# SCH.net
KiCad netlist of a schematic drawn in Altium Designer
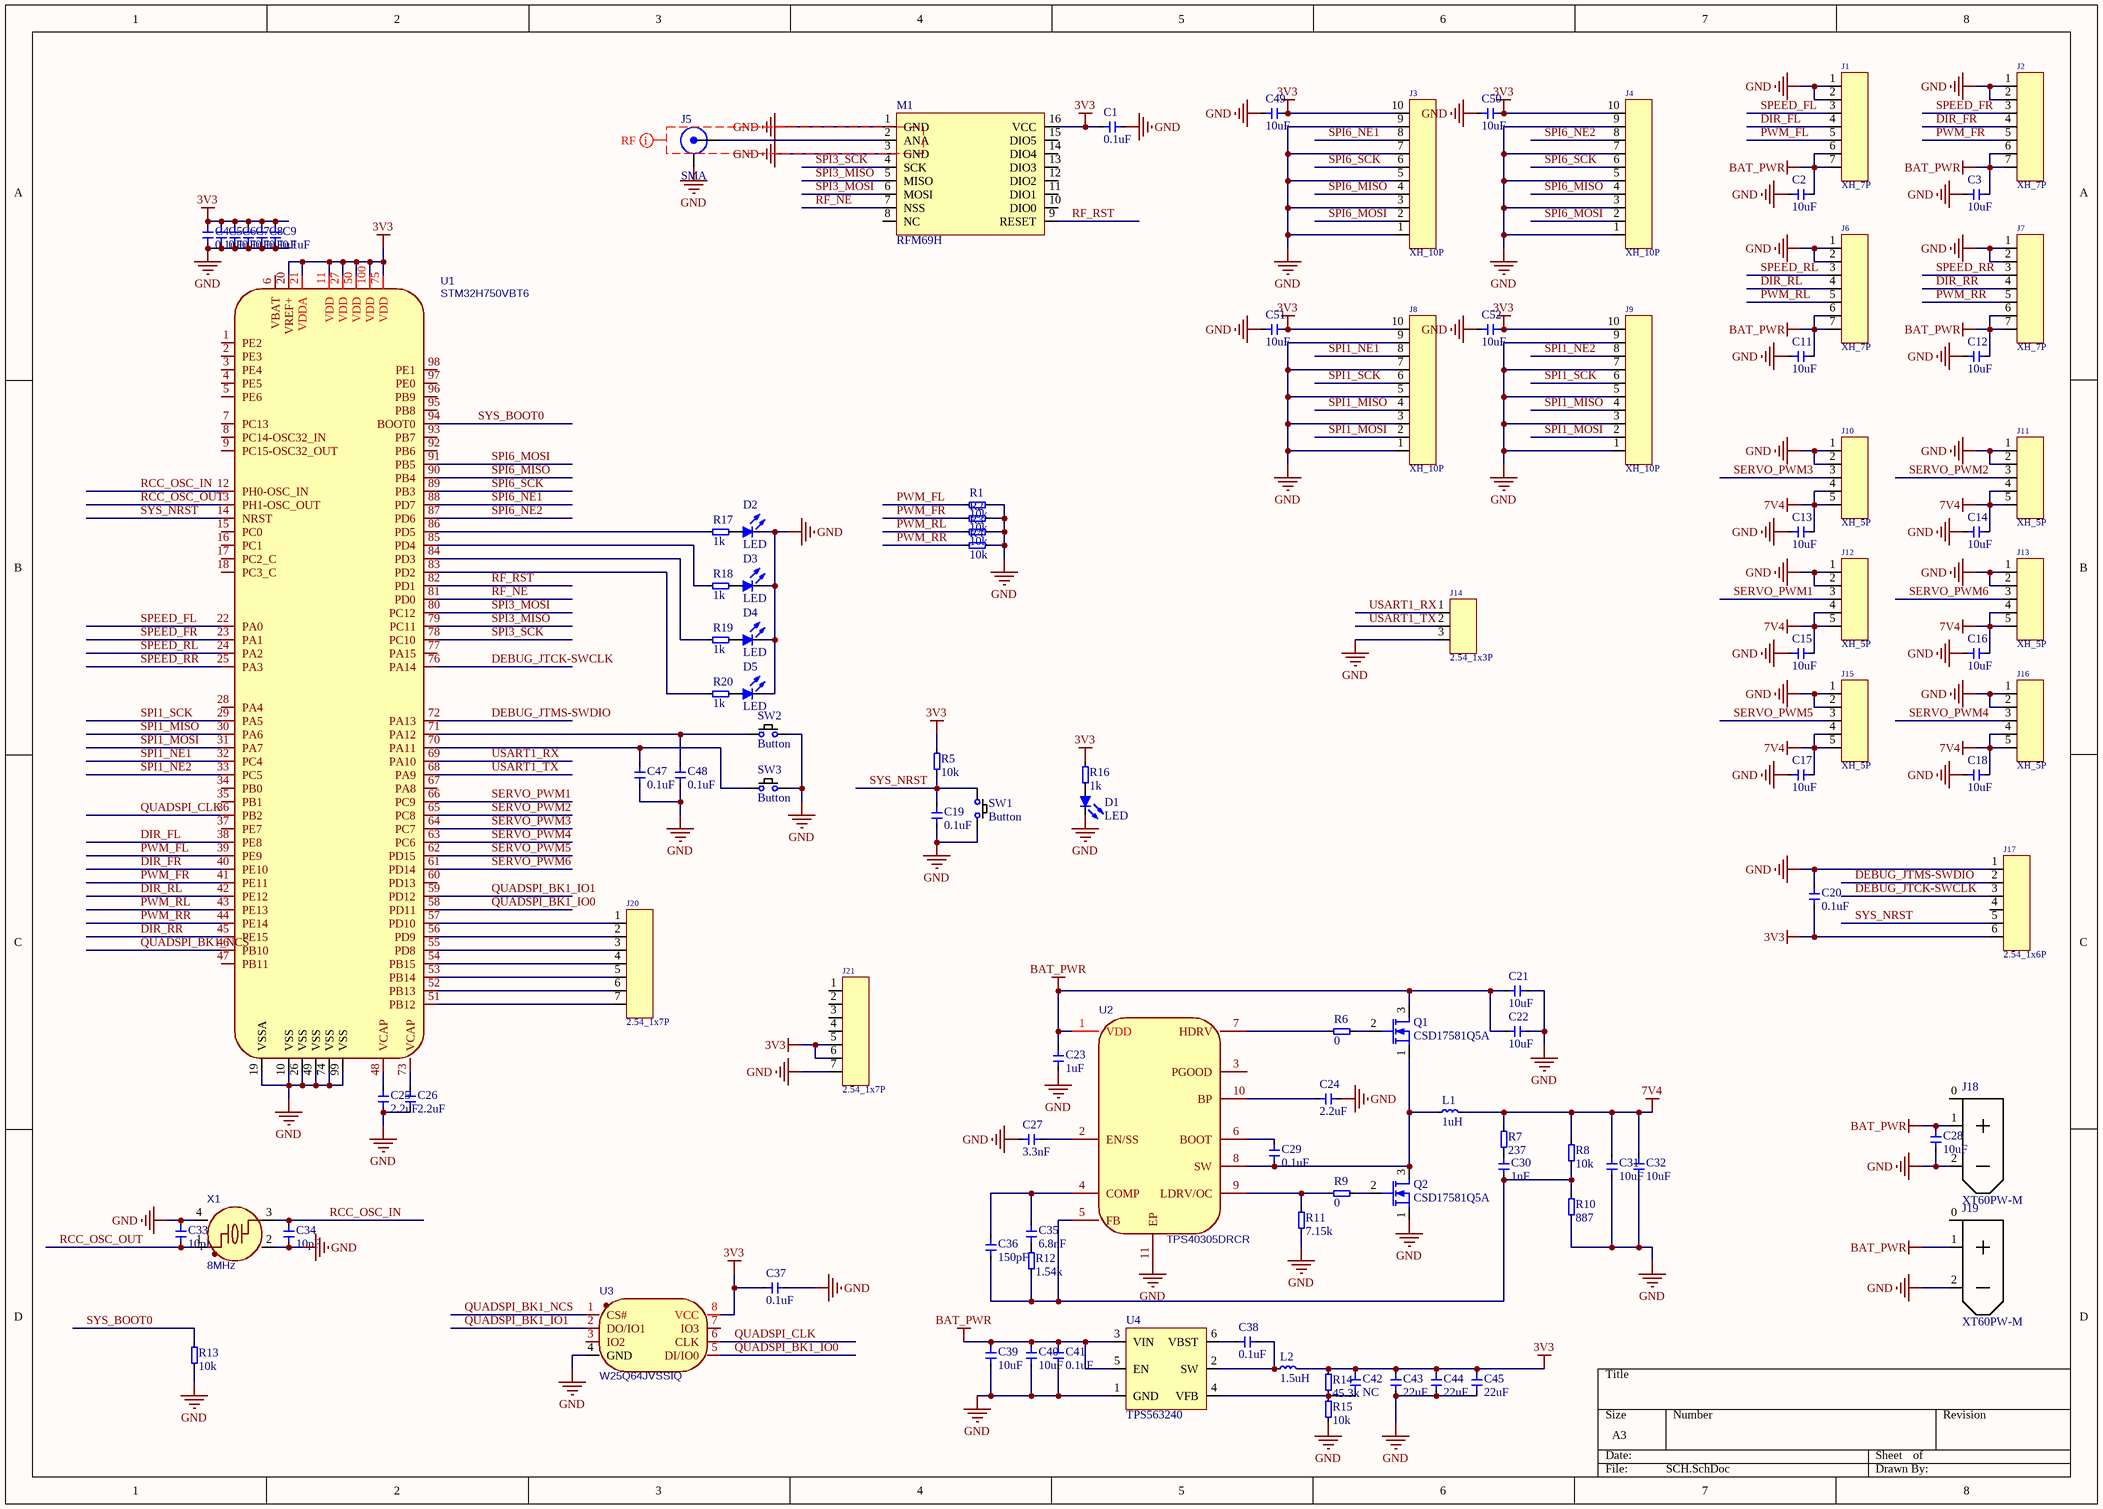
[diagram p0: SCH.SchDoc]

(export (version "E")
  (design (tool "Eeschema 10.0.6"))
  (components
    (comp (ref "C1") (value "0.1uF") (footprint "0402") (libsource (lib "pants1") (part "Cap")))
    (comp (ref "C2") (value "10uF") (footprint "0805") (libsource (lib "pants1") (part "Cap")))
    (comp (ref "C3") (value "10uF") (footprint "0805") (libsource (lib "pants1") (part "Cap")))
    (comp (ref "C4") (value "0.1uF") (footprint "0402") (libsource (lib "pants1") (part "Cap")))
    (comp (ref "C5") (value "0.1uF") (footprint "0402") (libsource (lib "pants1") (part "Cap")))
    (comp (ref "C6") (value "0.1uF") (footprint "0402") (libsource (lib "pants1") (part "Cap")))
    (comp (ref "C7") (value "0.1uF") (footprint "0402") (libsource (lib "pants1") (part "Cap")))
    (comp (ref "C8") (value "0.1uF") (footprint "0402") (libsource (lib "pants1") (part "Cap")))
    (comp (ref "C9") (value "0.1uF") (footprint "0402") (libsource (lib "pants1") (part "Cap")))
    (comp (ref "C11") (value "10uF") (footprint "0805") (libsource (lib "pants1") (part "Cap")))
    (comp (ref "C12") (value "10uF") (footprint "0805") (libsource (lib "pants1") (part "Cap")))
    (comp (ref "C13") (value "10uF") (footprint "0805") (libsource (lib "pants1") (part "Cap")))
    (comp (ref "C14") (value "10uF") (footprint "0805") (libsource (lib "pants1") (part "Cap")))
    (comp (ref "C15") (value "10uF") (footprint "0805") (libsource (lib "pants1") (part "Cap")))
    (comp (ref "C16") (value "10uF") (footprint "0805") (libsource (lib "pants1") (part "Cap")))
    (comp (ref "C17") (value "10uF") (footprint "0805") (libsource (lib "pants1") (part "Cap")))
    (comp (ref "C18") (value "10uF") (footprint "0805") (libsource (lib "pants1") (part "Cap")))
    (comp (ref "C19") (value "0.1uF") (footprint "0402") (libsource (lib "pants1") (part "Cap")))
    (comp (ref "C20") (value "0.1uF") (footprint "0402") (libsource (lib "pants1") (part "Cap")))
    (comp (ref "C21") (value "10uF") (footprint "0805") (libsource (lib "pants1") (part "Cap")))
    (comp (ref "C22") (value "10uF") (footprint "0805") (libsource (lib "pants1") (part "Cap")))
    (comp (ref "C23") (value "1uF") (footprint "0603") (libsource (lib "pants1") (part "Cap")))
    (comp (ref "C24") (value "2.2uF") (footprint "0603") (libsource (lib "pants1") (part "Cap")))
    (comp (ref "C25") (value "2.2uF") (footprint "0402") (libsource (lib "pants1") (part "Cap")))
    (comp (ref "C26") (value "2.2uF") (footprint "0402") (libsource (lib "pants1") (part "Cap")))
    (comp (ref "C27") (value "3.3nF") (footprint "0402") (libsource (lib "pants1") (part "Cap")))
    (comp (ref "C28") (value "10uF") (footprint "0805") (libsource (lib "pants1") (part "Cap")))
    (comp (ref "C29") (value "0.1uF") (footprint "0805") (libsource (lib "pants1") (part "Cap")))
    (comp (ref "C30") (value "1nF") (footprint "0402") (libsource (lib "pants1") (part "Cap")))
    (comp (ref "C31") (value "10uF") (footprint "0805") (libsource (lib "pants1") (part "Cap")))
    (comp (ref "C32") (value "10uF") (footprint "0805") (libsource (lib "pants1") (part "Cap")))
    (comp (ref "C33") (value "10pF") (footprint "0402") (libsource (lib "pants1") (part "Cap")))
    (comp (ref "C34") (value "10pF") (footprint "0402") (libsource (lib "pants1") (part "Cap")))
    (comp (ref "C35") (value "6.8nF") (footprint "0402") (libsource (lib "pants1") (part "Cap")))
    (comp (ref "C36") (value "150pF") (footprint "0402") (libsource (lib "pants1") (part "Cap")))
    (comp (ref "C37") (value "0.1uF") (footprint "0402") (libsource (lib "pants1") (part "Cap")))
    (comp (ref "C38") (value "0.1uF") (footprint "0603") (libsource (lib "pants1") (part "Cap")))
    (comp (ref "C39") (value "10uF") (footprint "0805") (libsource (lib "pants1") (part "Cap")))
    (comp (ref "C40") (value "10uF") (footprint "0805") (libsource (lib "pants1") (part "Cap")))
    (comp (ref "C41") (value "0.1uF") (footprint "0603") (libsource (lib "pants1") (part "Cap")))
    (comp (ref "C42") (value "NC") (footprint "0402") (libsource (lib "pants1") (part "Cap")))
    (comp (ref "C43") (value "22uF") (footprint "0603") (libsource (lib "pants1") (part "Cap")))
    (comp (ref "C44") (value "22uF") (footprint "0603") (libsource (lib "pants1") (part "Cap")))
    (comp (ref "C45") (value "22uF") (footprint "0603") (libsource (lib "pants1") (part "Cap")))
    (comp (ref "C47") (value "0.1uF") (footprint "0402") (libsource (lib "pants1") (part "Cap")))
    (comp (ref "C48") (value "0.1uF") (footprint "0402") (libsource (lib "pants1") (part "Cap")))
    (comp (ref "C49") (value "10uF") (footprint "0603") (libsource (lib "pants1") (part "Cap")))
    (comp (ref "C50") (value "10uF") (footprint "0603") (libsource (lib "pants1") (part "Cap")))
    (comp (ref "C51") (value "10uF") (footprint "0603") (libsource (lib "pants1") (part "Cap")))
    (comp (ref "C52") (value "10uF") (footprint "0603") (libsource (lib "pants1") (part "Cap")))
    (comp (ref "D1") (value "LED") (footprint "0603LED") (libsource (lib "pants1") (part "LED")))
    (comp (ref "D2") (value "LED") (footprint "0603LED") (libsource (lib "pants1") (part "LED")))
    (comp (ref "D3") (value "LED") (footprint "0603LED") (libsource (lib "pants1") (part "LED")))
    (comp (ref "D4") (value "LED") (footprint "0603LED") (libsource (lib "pants1") (part "LED")))
    (comp (ref "D5") (value "LED") (footprint "0603LED") (libsource (lib "pants1") (part "LED")))
    (comp (ref "J1") (value "XH_7P") (footprint "XH_7P直插立式") (libsource (lib "XH_Connectors") (part "XH_7P")))
    (comp (ref "J2") (value "XH_7P") (footprint "XH_7P直插立式") (libsource (lib "XH_Connectors") (part "XH_7P")))
    (comp (ref "J3")
      (value "XH_10P")
      (footprint "XH_10P直插立式")
      (libsource (lib "XH_Connectors") (part "XH_10P"))
    )
    (comp (ref "J4")
      (value "XH_10P")
      (footprint "XH_10P直插立式")
      (libsource (lib "XH_Connectors") (part "XH_10P"))
    )
    (comp (ref "J5") (value "SMA") (footprint "SMA_Edge") (libsource (lib "pants1") (part "Coax")))
    (comp (ref "J6") (value "XH_7P") (footprint "XH_7P直插立式") (libsource (lib "XH_Connectors") (part "XH_7P")))
    (comp (ref "J7") (value "XH_7P") (footprint "XH_7P直插立式") (libsource (lib "XH_Connectors") (part "XH_7P")))
    (comp (ref "J8")
      (value "XH_10P")
      (footprint "XH_10P直插立式")
      (libsource (lib "XH_Connectors") (part "XH_10P"))
    )
    (comp (ref "J9")
      (value "XH_10P")
      (footprint "XH_10P直插立式")
      (libsource (lib "XH_Connectors") (part "XH_10P"))
    )
    (comp (ref "J10")
      (value "XH_5P")
      (footprint "XH_5P直插立式")
      (libsource (lib "XH_Connectors") (part "XH_5P"))
    )
    (comp (ref "J11")
      (value "XH_5P")
      (footprint "XH_5P直插立式")
      (libsource (lib "XH_Connectors") (part "XH_5P"))
    )
    (comp (ref "J12")
      (value "XH_5P")
      (footprint "XH_5P直插立式")
      (libsource (lib "XH_Connectors") (part "XH_5P"))
    )
    (comp (ref "J13")
      (value "XH_5P")
      (footprint "XH_5P直插立式")
      (libsource (lib "XH_Connectors") (part "XH_5P"))
    )
    (comp (ref "J14")
      (value "2.54_1x3P")
      (footprint "2.54排针_1x3立式")
      (libsource (lib "2.54排针") (part "2.54_1x3P"))
    )
    (comp (ref "J15")
      (value "XH_5P")
      (footprint "XH_5P直插立式")
      (libsource (lib "XH_Connectors") (part "XH_5P"))
    )
    (comp (ref "J16")
      (value "XH_5P")
      (footprint "XH_5P直插立式")
      (libsource (lib "XH_Connectors") (part "XH_5P"))
    )
    (comp (ref "J17")
      (value "2.54_1x6P")
      (footprint "2.54排针_1x6立式")
      (libsource (lib "2.54排针") (part "2.54_1x6P"))
    )
    (comp (ref "J18") (value "XT60PW-M") (footprint "XT60PW-M20") (libsource (lib "XT60") (part "XT60PW-M")))
    (comp (ref "J19") (value "XT60PW-M") (footprint "XT60PW-M20") (libsource (lib "XT60") (part "XT60PW-M")))
    (comp (ref "J20")
      (value "2.54_1x7P")
      (footprint "2.54排针_1x7立式")
      (libsource (lib "2.54排针") (part "2.54_1x7P"))
    )
    (comp (ref "J21")
      (value "2.54_1x7P")
      (footprint "2.54排针_1x7立式")
      (libsource (lib "2.54排针") (part "2.54_1x7P"))
    )
    (comp (ref "L1")
      (value "1uH")
      (footprint "IND-SMD_L11.5-W10.5_1004")
      (description "Inductor")
      (libsource (lib "pants1") (part "Inductor"))
    )
    (comp (ref "L2")
      (value "1.5uH")
      (footprint "IND-SMD_L7.1-W6.6_0630")
      (description "Inductor")
      (libsource (lib "pants1") (part "Inductor"))
    )
    (comp (ref "M1") (value "RFM69H") (footprint "RFM69H") (libsource (lib "pants1") (part "RFM69H")))
    (comp (ref "Q1")
      (value "CSD17581Q5A")
      (footprint "SON-8_L5.0-W6.0-P1.27-BL_MOSFET")
      (libsource (lib "pants1") (part "MOS_N_SON8"))
    )
    (comp (ref "Q2")
      (value "CSD17581Q5A")
      (footprint "SON-8_L5.0-W6.0-P1.27-BL_MOSFET")
      (libsource (lib "pants1") (part "MOS_N_SON8"))
    )
    (comp (ref "R1")
      (value "10k")
      (footprint "0402")
      (description "Resistor")
      (libsource (lib "") (part "Res_1"))
    )
    (comp (ref "R2")
      (value "10k")
      (footprint "0402")
      (description "Resistor")
      (libsource (lib "") (part "Res_1"))
    )
    (comp (ref "R3")
      (value "10k")
      (footprint "0402")
      (description "Resistor")
      (libsource (lib "") (part "Res_1"))
    )
    (comp (ref "R4")
      (value "10k")
      (footprint "0402")
      (description "Resistor")
      (libsource (lib "") (part "Res_1"))
    )
    (comp (ref "R5")
      (value "10k")
      (footprint "0402")
      (description "Resistor")
      (libsource (lib "pants1") (part "Res"))
    )
    (comp (ref "R6")
      (value "0")
      (footprint "0402")
      (description "Resistor")
      (libsource (lib "") (part "Res_1"))
    )
    (comp (ref "R7")
      (value "237")
      (footprint "0402")
      (description "Resistor")
      (libsource (lib "pants1") (part "Res"))
    )
    (comp (ref "R8")
      (value "10k")
      (footprint "0402")
      (description "Resistor")
      (libsource (lib "pants1") (part "Res"))
    )
    (comp (ref "R9")
      (value "0")
      (footprint "0402")
      (description "Resistor")
      (libsource (lib "") (part "Res_1"))
    )
    (comp (ref "R10")
      (value "887")
      (footprint "0402")
      (description "Resistor")
      (libsource (lib "pants1") (part "Res"))
    )
    (comp (ref "R11")
      (value "7.15k")
      (footprint "0402")
      (description "Resistor")
      (libsource (lib "pants1") (part "Res"))
    )
    (comp (ref "R12")
      (value "1.54k")
      (footprint "0402")
      (description "Resistor")
      (libsource (lib "pants1") (part "Res"))
    )
    (comp (ref "R13")
      (value "10k")
      (footprint "0402")
      (description "Resistor")
      (libsource (lib "pants1") (part "Res"))
    )
    (comp (ref "R14")
      (value "45.3k")
      (footprint "0402")
      (description "Resistor")
      (libsource (lib "pants1") (part "Res"))
    )
    (comp (ref "R15")
      (value "10k")
      (footprint "0402")
      (description "Resistor")
      (libsource (lib "pants1") (part "Res"))
    )
    (comp (ref "R16")
      (value "1k")
      (footprint "0402")
      (description "Resistor")
      (libsource (lib "pants1") (part "Res"))
    )
    (comp (ref "R17")
      (value "1k")
      (footprint "0402")
      (description "Resistor")
      (libsource (lib "") (part "Res_2"))
    )
    (comp (ref "R18")
      (value "1k")
      (footprint "0402")
      (description "Resistor")
      (libsource (lib "") (part "Res_2"))
    )
    (comp (ref "R19")
      (value "1k")
      (footprint "0402")
      (description "Resistor")
      (libsource (lib "") (part "Res_2"))
    )
    (comp (ref "R20")
      (value "1k")
      (footprint "0402")
      (description "Resistor")
      (libsource (lib "") (part "Res_2"))
    )
    (comp (ref "SW1")
      (value "Button")
      (footprint "KEY-SMD_4P-L6.0-W6.0-P4.50-LS8.6")
      (libsource (lib "pants1") (part "Button"))
    )
    (comp (ref "SW2")
      (value "Button")
      (footprint "KEY-SMD_4P-L6.0-W6.0-P4.50-LS8.6")
      (libsource (lib "pants1") (part "Button"))
    )
    (comp (ref "SW3")
      (value "Button")
      (footprint "KEY-SMD_4P-L6.0-W6.0-P4.50-LS8.6")
      (libsource (lib "pants1") (part "Button"))
    )
    (comp (ref "U1")
      (value "STM32H750VBT6")
      (footprint "LQFP-100_L14.0-W14.0-P0.50-LS16.0-BL")
      (fields (field (name "BOM_SUPPLIER PART") "C404010") (field (name "CONTRIBUTOR") "LCSC"))
      (libsource (lib "pants1") (part "STM32H750VBT6"))
    )
    (comp (ref "U2")
      (value "TPS40305DRCR")
      (footprint "VSON-10_L3.0-W3.0-P0.50-TL-EP")
      (fields (field (name "BOM_SUPPLIER PART") "C140285") (field (name "CONTRIBUTOR") "LCSC"))
      (libsource (lib "pants1") (part "TPS40305DRCR"))
    )
    (comp (ref "U3")
      (value "W25Q64JVSSIQ")
      (footprint "SOP-8_L5.3-W5.3-P1.27-LS8.0-BL")
      (fields (field (name "BOM_SUPPLIER PART") "C83140"))
      (libsource (lib "pants1") (part "W25Q64JVSSIQ"))
    )
    (comp (ref "U4")
      (value "TPS563240")
      (footprint "SOT-23-6_L2.9-W1.6-P0.95-LS2.8-BR")
      (libsource (lib "pants1") (part "TPS563240"))
    )
    (comp (ref "X1")
      (value "8MHz")
      (footprint "OSC-SMD_4P-L3.2-W2.5-BL")
      (fields
        (field (name "BOM_SUPPLIER PART") "C518156")
        (field (name "BOM_MANUFACTURER PART") "3225-8.00-20-10-10/A")
        (field (name "CONTRIBUTOR") "LCSC")
      )
      (libsource (lib "pants1") (part "Crystal_4P"))
    )
  )
  (nets
    (net (code "1") (name "/DEBUG_JTCK-SWCLK") (class "Default")
      (node (ref "J17") (pin "3") (pinfunction "3_3") (pintype "passive"))
      (node (ref "U1") (pin "76") (pinfunction "PA14_76") (pintype "passive"))
    )
    (net (code "2") (name "/DEBUG_JTMS-SWDIO") (class "Default")
      (node (ref "J17") (pin "2") (pinfunction "2_2") (pintype "passive"))
      (node (ref "U1") (pin "72") (pinfunction "PA13_72") (pintype "passive"))
    )
    (net (code "3") (name "/DIR_FL") (class "Default")
      (node (ref "J1") (pin "4") (pinfunction "4_4") (pintype "passive"))
      (node (ref "U1") (pin "38") (pinfunction "PE8_38") (pintype "passive"))
    )
    (net (code "4") (name "/DIR_FR") (class "Default")
      (node (ref "J2") (pin "4") (pinfunction "4_4") (pintype "passive"))
      (node (ref "U1") (pin "40") (pinfunction "PE10_40") (pintype "passive"))
    )
    (net (code "5") (name "/DIR_RL") (class "Default")
      (node (ref "J6") (pin "4") (pinfunction "4_4") (pintype "passive"))
      (node (ref "U1") (pin "42") (pinfunction "PE12_42") (pintype "passive"))
    )
    (net (code "6") (name "/DIR_RR") (class "Default")
      (node (ref "J7") (pin "4") (pinfunction "4_4") (pintype "passive"))
      (node (ref "U1") (pin "45") (pinfunction "PE15_45") (pintype "passive"))
    )
    (net (code "7") (name "/PWM_FL") (class "Default")
      (node (ref "J1") (pin "5") (pinfunction "5_5") (pintype "passive"))
      (node (ref "R1") (pin "1") (pinfunction "1_1") (pintype "passive"))
      (node (ref "U1") (pin "39") (pinfunction "PE9_39") (pintype "passive"))
    )
    (net (code "8") (name "/PWM_FR") (class "Default")
      (node (ref "J2") (pin "5") (pinfunction "5_5") (pintype "passive"))
      (node (ref "R2") (pin "1") (pinfunction "1_1") (pintype "passive"))
      (node (ref "U1") (pin "41") (pinfunction "PE11_41") (pintype "passive"))
    )
    (net (code "9") (name "/PWM_RL") (class "Default")
      (node (ref "J6") (pin "5") (pinfunction "5_5") (pintype "passive"))
      (node (ref "R3") (pin "1") (pinfunction "1_1") (pintype "passive"))
      (node (ref "U1") (pin "43") (pinfunction "PE13_43") (pintype "passive"))
    )
    (net (code "10") (name "/PWM_RR") (class "Default")
      (node (ref "J7") (pin "5") (pinfunction "5_5") (pintype "passive"))
      (node (ref "R4") (pin "1") (pinfunction "1_1") (pintype "passive"))
      (node (ref "U1") (pin "44") (pinfunction "PE14_44") (pintype "passive"))
    )
    (net (code "11") (name "/QUADSPI_BK1_IO0") (class "Default")
      (node (ref "U1") (pin "58") (pinfunction "PD11_58") (pintype "passive"))
      (node (ref "U3") (pin "5") (pinfunction "DI/IO0_5") (pintype "passive"))
    )
    (net (code "12") (name "/QUADSPI_BK1_IO1") (class "Default")
      (node (ref "U1") (pin "59") (pinfunction "PD12_59") (pintype "passive"))
      (node (ref "U3") (pin "2") (pinfunction "DO/IO1_2") (pintype "passive"))
    )
    (net (code "13") (name "/QUADSPI_BK1_NCS") (class "Default")
      (node (ref "U1") (pin "46") (pinfunction "PB10_46") (pintype "passive"))
      (node (ref "U3") (pin "1") (pinfunction "CS#_1") (pintype "passive"))
    )
    (net (code "14") (name "/QUADSPI_CLK") (class "Default")
      (node (ref "U1") (pin "36") (pinfunction "PB2_36") (pintype "passive"))
      (node (ref "U3") (pin "6") (pinfunction "CLK_6") (pintype "passive"))
    )
    (net (code "15") (name "/RCC_OSC_IN") (class "Default")
      (node (ref "C34") (pin "2") (pinfunction "2_2") (pintype "passive"))
      (node (ref "U1") (pin "12") (pinfunction "PH0-OSC_IN_12") (pintype "passive"))
      (node (ref "X1") (pin "3") (pinfunction "3_3") (pintype "passive"))
    )
    (net (code "16") (name "/RCC_OSC_OUT") (class "Default")
      (node (ref "C33") (pin "1") (pinfunction "1_1") (pintype "passive"))
      (node (ref "U1") (pin "13") (pinfunction "PH1-OSC_OUT_13") (pintype "passive"))
      (node (ref "X1") (pin "1") (pinfunction "1_1") (pintype "passive"))
    )
    (net (code "17") (name "/RF_NE") (class "Default")
      (node (ref "M1") (pin "7") (pinfunction "NSS_7") (pintype "passive"))
      (node (ref "U1") (pin "81") (pinfunction "PD0_81") (pintype "passive"))
    )
    (net (code "18") (name "/RF_RST") (class "Default")
      (node (ref "M1") (pin "9") (pinfunction "RESET_9") (pintype "passive"))
      (node (ref "U1") (pin "82") (pinfunction "PD1_82") (pintype "passive"))
    )
    (net (code "19") (name "/SERVO_PWM1") (class "Default")
      (node (ref "J12") (pin "3") (pinfunction "3_3") (pintype "passive"))
      (node (ref "U1") (pin "66") (pinfunction "PC9_66") (pintype "passive"))
    )
    (net (code "20") (name "/SERVO_PWM2") (class "Default")
      (node (ref "J11") (pin "3") (pinfunction "3_3") (pintype "passive"))
      (node (ref "U1") (pin "65") (pinfunction "PC8_65") (pintype "passive"))
    )
    (net (code "21") (name "/SERVO_PWM3") (class "Default")
      (node (ref "J10") (pin "3") (pinfunction "3_3") (pintype "passive"))
      (node (ref "U1") (pin "64") (pinfunction "PC7_64") (pintype "passive"))
    )
    (net (code "22") (name "/SERVO_PWM4") (class "Default")
      (node (ref "J16") (pin "3") (pinfunction "3_3") (pintype "passive"))
      (node (ref "U1") (pin "63") (pinfunction "PC6_63") (pintype "passive"))
    )
    (net (code "23") (name "/SERVO_PWM5") (class "Default")
      (node (ref "J15") (pin "3") (pinfunction "3_3") (pintype "passive"))
      (node (ref "U1") (pin "62") (pinfunction "PD15_62") (pintype "passive"))
    )
    (net (code "24") (name "/SERVO_PWM6") (class "Default")
      (node (ref "J13") (pin "3") (pinfunction "3_3") (pintype "passive"))
      (node (ref "U1") (pin "61") (pinfunction "PD14_61") (pintype "passive"))
    )
    (net (code "25") (name "/SPEED_FL") (class "Default")
      (node (ref "J1") (pin "3") (pinfunction "3_3") (pintype "passive"))
      (node (ref "U1") (pin "22") (pinfunction "PA0_22") (pintype "passive"))
    )
    (net (code "26") (name "/SPEED_FR") (class "Default")
      (node (ref "J2") (pin "3") (pinfunction "3_3") (pintype "passive"))
      (node (ref "U1") (pin "23") (pinfunction "PA1_23") (pintype "passive"))
    )
    (net (code "27") (name "/SPEED_RL") (class "Default")
      (node (ref "J6") (pin "3") (pinfunction "3_3") (pintype "passive"))
      (node (ref "U1") (pin "24") (pinfunction "PA2_24") (pintype "passive"))
    )
    (net (code "28") (name "/SPEED_RR") (class "Default")
      (node (ref "J7") (pin "3") (pinfunction "3_3") (pintype "passive"))
      (node (ref "U1") (pin "25") (pinfunction "PA3_25") (pintype "passive"))
    )
    (net (code "29") (name "/SPI1_MISO") (class "Default")
      (node (ref "J8") (pin "4") (pinfunction "4_4") (pintype "passive"))
      (node (ref "J9") (pin "4") (pinfunction "4_4") (pintype "passive"))
      (node (ref "U1") (pin "30") (pinfunction "PA6_30") (pintype "passive"))
    )
    (net (code "30") (name "/SPI1_MOSI") (class "Default")
      (node (ref "J8") (pin "2") (pinfunction "2_2") (pintype "passive"))
      (node (ref "J9") (pin "2") (pinfunction "2_2") (pintype "passive"))
      (node (ref "U1") (pin "31") (pinfunction "PA7_31") (pintype "passive"))
    )
    (net (code "31") (name "/SPI1_NE1") (class "Default")
      (node (ref "J8") (pin "8") (pinfunction "8_8") (pintype "passive"))
      (node (ref "U1") (pin "32") (pinfunction "PC4_32") (pintype "passive"))
    )
    (net (code "32") (name "/SPI1_NE2") (class "Default")
      (node (ref "J9") (pin "8") (pinfunction "8_8") (pintype "passive"))
      (node (ref "U1") (pin "33") (pinfunction "PC5_33") (pintype "passive"))
    )
    (net (code "33") (name "/SPI1_SCK") (class "Default")
      (node (ref "J8") (pin "6") (pinfunction "6_6") (pintype "passive"))
      (node (ref "J9") (pin "6") (pinfunction "6_6") (pintype "passive"))
      (node (ref "U1") (pin "29") (pinfunction "PA5_29") (pintype "passive"))
    )
    (net (code "34") (name "/SPI3_MISO") (class "Default")
      (node (ref "M1") (pin "5") (pinfunction "MISO_5") (pintype "passive"))
      (node (ref "U1") (pin "79") (pinfunction "PC11_79") (pintype "passive"))
    )
    (net (code "35") (name "/SPI3_MOSI") (class "Default")
      (node (ref "M1") (pin "6") (pinfunction "MOSI_6") (pintype "passive"))
      (node (ref "U1") (pin "80") (pinfunction "PC12_80") (pintype "passive"))
    )
    (net (code "36") (name "/SPI3_SCK") (class "Default")
      (node (ref "M1") (pin "4") (pinfunction "SCK_4") (pintype "passive"))
      (node (ref "U1") (pin "78") (pinfunction "PC10_78") (pintype "passive"))
    )
    (net (code "37") (name "/SPI6_MISO") (class "Default")
      (node (ref "J3") (pin "4") (pinfunction "4_4") (pintype "passive"))
      (node (ref "J4") (pin "4") (pinfunction "4_4") (pintype "passive"))
      (node (ref "U1") (pin "90") (pinfunction "PB4_90") (pintype "passive"))
    )
    (net (code "38") (name "/SPI6_MOSI") (class "Default")
      (node (ref "J3") (pin "2") (pinfunction "2_2") (pintype "passive"))
      (node (ref "J4") (pin "2") (pinfunction "2_2") (pintype "passive"))
      (node (ref "U1") (pin "91") (pinfunction "PB5_91") (pintype "passive"))
    )
    (net (code "39") (name "/SPI6_NE1") (class "Default")
      (node (ref "J3") (pin "8") (pinfunction "8_8") (pintype "passive"))
      (node (ref "U1") (pin "88") (pinfunction "PD7_88") (pintype "passive"))
    )
    (net (code "40") (name "/SPI6_NE2") (class "Default")
      (node (ref "J4") (pin "8") (pinfunction "8_8") (pintype "passive"))
      (node (ref "U1") (pin "87") (pinfunction "PD6_87") (pintype "passive"))
    )
    (net (code "41") (name "/SPI6_SCK") (class "Default")
      (node (ref "J3") (pin "6") (pinfunction "6_6") (pintype "passive"))
      (node (ref "J4") (pin "6") (pinfunction "6_6") (pintype "passive"))
      (node (ref "U1") (pin "89") (pinfunction "PB3_89") (pintype "passive"))
    )
    (net (code "42") (name "/SYS_BOOT0") (class "Default")
      (node (ref "R13") (pin "2") (pinfunction "2_2") (pintype "passive"))
      (node (ref "U1") (pin "94") (pinfunction "BOOT0_94") (pintype "passive"))
    )
    (net (code "43") (name "/SYS_NRST") (class "Default")
      (node (ref "C19") (pin "2") (pinfunction "2_2") (pintype "passive"))
      (node (ref "J17") (pin "5") (pinfunction "5_5") (pintype "passive"))
      (node (ref "R5") (pin "1") (pinfunction "1_1") (pintype "passive"))
      (node (ref "SW1") (pin "1") (pinfunction "1_1") (pintype "passive"))
      (node (ref "U1") (pin "14") (pinfunction "NRST_14") (pintype "passive"))
    )
    (net (code "44") (name "/USART1_RX") (class "Default")
      (node (ref "J14") (pin "1") (pinfunction "1_1") (pintype "passive"))
      (node (ref "U1") (pin "69") (pinfunction "PA10_69") (pintype "passive"))
    )
    (net (code "45") (name "/USART1_TX") (class "Default")
      (node (ref "J14") (pin "2") (pinfunction "2_2") (pintype "passive"))
      (node (ref "U1") (pin "68") (pinfunction "PA9_68") (pintype "passive"))
    )
    (net (code "46") (name "3V3") (class "Default")
      (node (ref "C1") (pin "2") (pinfunction "2_2") (pintype "passive"))
      (node (ref "C20") (pin "1") (pinfunction "1_1") (pintype "passive"))
      (node (ref "C37") (pin "1") (pinfunction "1_1") (pintype "passive"))
      (node (ref "C4") (pin "2") (pinfunction "2_2") (pintype "passive"))
      (node (ref "C42") (pin "2") (pinfunction "2_2") (pintype "passive"))
      (node (ref "C43") (pin "2") (pinfunction "2_2") (pintype "passive"))
      (node (ref "C44") (pin "2") (pinfunction "2_2") (pintype "passive"))
      (node (ref "C45") (pin "2") (pinfunction "2_2") (pintype "passive"))
      (node (ref "C49") (pin "2") (pinfunction "2_2") (pintype "passive"))
      (node (ref "C5") (pin "2") (pinfunction "2_2") (pintype "passive"))
      (node (ref "C50") (pin "2") (pinfunction "2_2") (pintype "passive"))
      (node (ref "C51") (pin "2") (pinfunction "2_2") (pintype "passive"))
      (node (ref "C52") (pin "2") (pinfunction "2_2") (pintype "passive"))
      (node (ref "C6") (pin "2") (pinfunction "2_2") (pintype "passive"))
      (node (ref "C7") (pin "2") (pinfunction "2_2") (pintype "passive"))
      (node (ref "C8") (pin "2") (pinfunction "2_2") (pintype "passive"))
      (node (ref "C9") (pin "2") (pinfunction "2_2") (pintype "passive"))
      (node (ref "J17") (pin "6") (pinfunction "6_6") (pintype "passive"))
      (node (ref "J21") (pin "5") (pinfunction "5_5") (pintype "passive"))
      (node (ref "J21") (pin "6") (pinfunction "6_6") (pintype "passive"))
      (node (ref "J3") (pin "10") (pinfunction "10_10") (pintype "passive"))
      (node (ref "J4") (pin "10") (pinfunction "10_10") (pintype "passive"))
      (node (ref "J8") (pin "10") (pinfunction "10_10") (pintype "passive"))
      (node (ref "J9") (pin "10") (pinfunction "10_10") (pintype "passive"))
      (node (ref "L2") (pin "2") (pinfunction "2_2") (pintype "passive"))
      (node (ref "M1") (pin "16") (pinfunction "VCC_16") (pintype "passive"))
      (node (ref "R14") (pin "2") (pinfunction "2_2") (pintype "passive"))
      (node (ref "R16") (pin "2") (pinfunction "2_2") (pintype "passive"))
      (node (ref "R5") (pin "2") (pinfunction "2_2") (pintype "passive"))
      (node (ref "U1") (pin "100") (pinfunction "VDD_100") (pintype "passive"))
      (node (ref "U1") (pin "11") (pinfunction "VDD_11") (pintype "passive"))
      (node (ref "U1") (pin "20") (pinfunction "VREF+_20") (pintype "passive"))
      (node (ref "U1") (pin "21") (pinfunction "VDDA_21") (pintype "passive"))
      (node (ref "U1") (pin "27") (pinfunction "VDD_27") (pintype "passive"))
      (node (ref "U1") (pin "50") (pinfunction "VDD_50") (pintype "passive"))
      (node (ref "U1") (pin "75") (pinfunction "VDD_75") (pintype "passive"))
      (node (ref "U3") (pin "8") (pinfunction "VCC_8") (pintype "passive"))
    )
    (net (code "47") (name "7V4") (class "Default")
      (node (ref "C13") (pin "2") (pinfunction "2_2") (pintype "passive"))
      (node (ref "C14") (pin "2") (pinfunction "2_2") (pintype "passive"))
      (node (ref "C15") (pin "2") (pinfunction "2_2") (pintype "passive"))
      (node (ref "C16") (pin "2") (pinfunction "2_2") (pintype "passive"))
      (node (ref "C17") (pin "2") (pinfunction "2_2") (pintype "passive"))
      (node (ref "C18") (pin "2") (pinfunction "2_2") (pintype "passive"))
      (node (ref "C31") (pin "1") (pinfunction "1_1") (pintype "passive"))
      (node (ref "C32") (pin "1") (pinfunction "1_1") (pintype "passive"))
      (node (ref "J10") (pin "4") (pinfunction "4_4") (pintype "passive"))
      (node (ref "J10") (pin "5") (pinfunction "5_5") (pintype "passive"))
      (node (ref "J11") (pin "4") (pinfunction "4_4") (pintype "passive"))
      (node (ref "J11") (pin "5") (pinfunction "5_5") (pintype "passive"))
      (node (ref "J12") (pin "4") (pinfunction "4_4") (pintype "passive"))
      (node (ref "J12") (pin "5") (pinfunction "5_5") (pintype "passive"))
      (node (ref "J13") (pin "4") (pinfunction "4_4") (pintype "passive"))
      (node (ref "J13") (pin "5") (pinfunction "5_5") (pintype "passive"))
      (node (ref "J15") (pin "4") (pinfunction "4_4") (pintype "passive"))
      (node (ref "J15") (pin "5") (pinfunction "5_5") (pintype "passive"))
      (node (ref "J16") (pin "4") (pinfunction "4_4") (pintype "passive"))
      (node (ref "J16") (pin "5") (pinfunction "5_5") (pintype "passive"))
      (node (ref "L1") (pin "2") (pinfunction "2_2") (pintype "passive"))
      (node (ref "R7") (pin "2") (pinfunction "2_2") (pintype "passive"))
      (node (ref "R8") (pin "2") (pinfunction "2_2") (pintype "passive"))
    )
    (net (code "48") (name "BAT_PWR") (class "Default")
      (node (ref "C11") (pin "2") (pinfunction "2_2") (pintype "passive"))
      (node (ref "C12") (pin "2") (pinfunction "2_2") (pintype "passive"))
      (node (ref "C2") (pin "2") (pinfunction "2_2") (pintype "passive"))
      (node (ref "C21") (pin "2") (pinfunction "2_2") (pintype "passive"))
      (node (ref "C22") (pin "2") (pinfunction "2_2") (pintype "passive"))
      (node (ref "C23") (pin "2") (pinfunction "2_2") (pintype "passive"))
      (node (ref "C28") (pin "1") (pinfunction "1_1") (pintype "passive"))
      (node (ref "C3") (pin "2") (pinfunction "2_2") (pintype "passive"))
      (node (ref "C39") (pin "2") (pinfunction "2_2") (pintype "passive"))
      (node (ref "C40") (pin "2") (pinfunction "2_2") (pintype "passive"))
      (node (ref "C41") (pin "1") (pinfunction "1_1") (pintype "passive"))
      (node (ref "J1") (pin "6") (pinfunction "6_6") (pintype "passive"))
      (node (ref "J1") (pin "7") (pinfunction "7_7") (pintype "passive"))
      (node (ref "J18") (pin "1") (pinfunction "1_1") (pintype "passive"))
      (node (ref "J19") (pin "1") (pinfunction "1_1") (pintype "passive"))
      (node (ref "J2") (pin "6") (pinfunction "6_6") (pintype "passive"))
      (node (ref "J2") (pin "7") (pinfunction "7_7") (pintype "passive"))
      (node (ref "J6") (pin "6") (pinfunction "6_6") (pintype "passive"))
      (node (ref "J6") (pin "7") (pinfunction "7_7") (pintype "passive"))
      (node (ref "J7") (pin "6") (pinfunction "6_6") (pintype "passive"))
      (node (ref "J7") (pin "7") (pinfunction "7_7") (pintype "passive"))
      (node (ref "Q1") (pin "3") (pinfunction "D_3") (pintype "passive"))
      (node (ref "U2") (pin "1") (pinfunction "VDD_1") (pintype "passive"))
      (node (ref "U4") (pin "3") (pinfunction "VIN_3") (pintype "passive"))
      (node (ref "U4") (pin "5") (pinfunction "EN_5") (pintype "passive"))
    )
    (net (code "49") (name "GND") (class "Default")
      (node (ref "C1") (pin "1") (pinfunction "1_1") (pintype "passive"))
      (node (ref "C11") (pin "1") (pinfunction "1_1") (pintype "passive"))
      (node (ref "C12") (pin "1") (pinfunction "1_1") (pintype "passive"))
      (node (ref "C13") (pin "1") (pinfunction "1_1") (pintype "passive"))
      (node (ref "C14") (pin "1") (pinfunction "1_1") (pintype "passive"))
      (node (ref "C15") (pin "1") (pinfunction "1_1") (pintype "passive"))
      (node (ref "C16") (pin "1") (pinfunction "1_1") (pintype "passive"))
      (node (ref "C17") (pin "1") (pinfunction "1_1") (pintype "passive"))
      (node (ref "C18") (pin "1") (pinfunction "1_1") (pintype "passive"))
      (node (ref "C19") (pin "1") (pinfunction "1_1") (pintype "passive"))
      (node (ref "C2") (pin "1") (pinfunction "1_1") (pintype "passive"))
      (node (ref "C20") (pin "2") (pinfunction "2_2") (pintype "passive"))
      (node (ref "C21") (pin "1") (pinfunction "1_1") (pintype "passive"))
      (node (ref "C22") (pin "1") (pinfunction "1_1") (pintype "passive"))
      (node (ref "C23") (pin "1") (pinfunction "1_1") (pintype "passive"))
      (node (ref "C24") (pin "2") (pinfunction "2_2") (pintype "passive"))
      (node (ref "C25") (pin "1") (pinfunction "1_1") (pintype "passive"))
      (node (ref "C26") (pin "1") (pinfunction "1_1") (pintype "passive"))
      (node (ref "C27") (pin "2") (pinfunction "2_2") (pintype "passive"))
      (node (ref "C28") (pin "2") (pinfunction "2_2") (pintype "passive"))
      (node (ref "C3") (pin "1") (pinfunction "1_1") (pintype "passive"))
      (node (ref "C31") (pin "2") (pinfunction "2_2") (pintype "passive"))
      (node (ref "C32") (pin "2") (pinfunction "2_2") (pintype "passive"))
      (node (ref "C33") (pin "2") (pinfunction "2_2") (pintype "passive"))
      (node (ref "C34") (pin "1") (pinfunction "1_1") (pintype "passive"))
      (node (ref "C37") (pin "2") (pinfunction "2_2") (pintype "passive"))
      (node (ref "C39") (pin "1") (pinfunction "1_1") (pintype "passive"))
      (node (ref "C4") (pin "1") (pinfunction "1_1") (pintype "passive"))
      (node (ref "C40") (pin "1") (pinfunction "1_1") (pintype "passive"))
      (node (ref "C41") (pin "2") (pinfunction "2_2") (pintype "passive"))
      (node (ref "C43") (pin "1") (pinfunction "1_1") (pintype "passive"))
      (node (ref "C44") (pin "1") (pinfunction "1_1") (pintype "passive"))
      (node (ref "C45") (pin "1") (pinfunction "1_1") (pintype "passive"))
      (node (ref "C47") (pin "2") (pinfunction "2_2") (pintype "passive"))
      (node (ref "C48") (pin "2") (pinfunction "2_2") (pintype "passive"))
      (node (ref "C49") (pin "1") (pinfunction "1_1") (pintype "passive"))
      (node (ref "C5") (pin "1") (pinfunction "1_1") (pintype "passive"))
      (node (ref "C50") (pin "1") (pinfunction "1_1") (pintype "passive"))
      (node (ref "C51") (pin "1") (pinfunction "1_1") (pintype "passive"))
      (node (ref "C52") (pin "1") (pinfunction "1_1") (pintype "passive"))
      (node (ref "C6") (pin "1") (pinfunction "1_1") (pintype "passive"))
      (node (ref "C7") (pin "1") (pinfunction "1_1") (pintype "passive"))
      (node (ref "C8") (pin "1") (pinfunction "1_1") (pintype "passive"))
      (node (ref "C9") (pin "1") (pinfunction "1_1") (pintype "passive"))
      (node (ref "D1") (pin "K") (pinfunction "K_K") (pintype "passive"))
      (node (ref "D2") (pin "K") (pinfunction "K_K") (pintype "passive"))
      (node (ref "D3") (pin "K") (pinfunction "K_K") (pintype "passive"))
      (node (ref "D4") (pin "K") (pinfunction "K_K") (pintype "passive"))
      (node (ref "D5") (pin "K") (pinfunction "K_K") (pintype "passive"))
      (node (ref "J1") (pin "1") (pinfunction "1_1") (pintype "passive"))
      (node (ref "J1") (pin "2") (pinfunction "2_2") (pintype "passive"))
      (node (ref "J10") (pin "1") (pinfunction "1_1") (pintype "passive"))
      (node (ref "J10") (pin "2") (pinfunction "2_2") (pintype "passive"))
      (node (ref "J11") (pin "1") (pinfunction "1_1") (pintype "passive"))
      (node (ref "J11") (pin "2") (pinfunction "2_2") (pintype "passive"))
      (node (ref "J12") (pin "1") (pinfunction "1_1") (pintype "passive"))
      (node (ref "J12") (pin "2") (pinfunction "2_2") (pintype "passive"))
      (node (ref "J13") (pin "1") (pinfunction "1_1") (pintype "passive"))
      (node (ref "J13") (pin "2") (pinfunction "2_2") (pintype "passive"))
      (node (ref "J14") (pin "3") (pinfunction "3_3") (pintype "passive"))
      (node (ref "J15") (pin "1") (pinfunction "1_1") (pintype "passive"))
      (node (ref "J15") (pin "2") (pinfunction "2_2") (pintype "passive"))
      (node (ref "J16") (pin "1") (pinfunction "1_1") (pintype "passive"))
      (node (ref "J16") (pin "2") (pinfunction "2_2") (pintype "passive"))
      (node (ref "J17") (pin "1") (pinfunction "1_1") (pintype "passive"))
      (node (ref "J18") (pin "2") (pinfunction "2_2") (pintype "passive"))
      (node (ref "J19") (pin "2") (pinfunction "2_2") (pintype "passive"))
      (node (ref "J2") (pin "1") (pinfunction "1_1") (pintype "passive"))
      (node (ref "J2") (pin "2") (pinfunction "2_2") (pintype "passive"))
      (node (ref "J21") (pin "7") (pinfunction "7_7") (pintype "passive"))
      (node (ref "J3") (pin "1") (pinfunction "1_1") (pintype "passive"))
      (node (ref "J3") (pin "3") (pinfunction "3_3") (pintype "passive"))
      (node (ref "J3") (pin "5") (pinfunction "5_5") (pintype "passive"))
      (node (ref "J3") (pin "7") (pinfunction "7_7") (pintype "passive"))
      (node (ref "J3") (pin "9") (pinfunction "9_9") (pintype "passive"))
      (node (ref "J4") (pin "1") (pinfunction "1_1") (pintype "passive"))
      (node (ref "J4") (pin "3") (pinfunction "3_3") (pintype "passive"))
      (node (ref "J4") (pin "5") (pinfunction "5_5") (pintype "passive"))
      (node (ref "J4") (pin "7") (pinfunction "7_7") (pintype "passive"))
      (node (ref "J4") (pin "9") (pinfunction "9_9") (pintype "passive"))
      (node (ref "J5") (pin "2") (pintype "passive"))
      (node (ref "J6") (pin "1") (pinfunction "1_1") (pintype "passive"))
      (node (ref "J6") (pin "2") (pinfunction "2_2") (pintype "passive"))
      (node (ref "J7") (pin "1") (pinfunction "1_1") (pintype "passive"))
      (node (ref "J7") (pin "2") (pinfunction "2_2") (pintype "passive"))
      (node (ref "J8") (pin "1") (pinfunction "1_1") (pintype "passive"))
      (node (ref "J8") (pin "3") (pinfunction "3_3") (pintype "passive"))
      (node (ref "J8") (pin "5") (pinfunction "5_5") (pintype "passive"))
      (node (ref "J8") (pin "7") (pinfunction "7_7") (pintype "passive"))
      (node (ref "J8") (pin "9") (pinfunction "9_9") (pintype "passive"))
      (node (ref "J9") (pin "1") (pinfunction "1_1") (pintype "passive"))
      (node (ref "J9") (pin "3") (pinfunction "3_3") (pintype "passive"))
      (node (ref "J9") (pin "5") (pinfunction "5_5") (pintype "passive"))
      (node (ref "J9") (pin "7") (pinfunction "7_7") (pintype "passive"))
      (node (ref "J9") (pin "9") (pinfunction "9_9") (pintype "passive"))
      (node (ref "M1") (pin "1") (pinfunction "GND_1") (pintype "passive"))
      (node (ref "M1") (pin "3") (pinfunction "GND_3") (pintype "passive"))
      (node (ref "Q2") (pin "1") (pinfunction "S_1") (pintype "passive"))
      (node (ref "R1") (pin "2") (pinfunction "2_2") (pintype "passive"))
      (node (ref "R10") (pin "1") (pinfunction "1_1") (pintype "passive"))
      (node (ref "R11") (pin "1") (pinfunction "1_1") (pintype "passive"))
      (node (ref "R13") (pin "1") (pinfunction "1_1") (pintype "passive"))
      (node (ref "R15") (pin "1") (pinfunction "1_1") (pintype "passive"))
      (node (ref "R2") (pin "2") (pinfunction "2_2") (pintype "passive"))
      (node (ref "R3") (pin "2") (pinfunction "2_2") (pintype "passive"))
      (node (ref "R4") (pin "2") (pinfunction "2_2") (pintype "passive"))
      (node (ref "SW1") (pin "2") (pinfunction "2_2") (pintype "passive"))
      (node (ref "SW2") (pin "2") (pinfunction "2_2") (pintype "passive"))
      (node (ref "SW3") (pin "2") (pinfunction "2_2") (pintype "passive"))
      (node (ref "U1") (pin "10") (pinfunction "VSS_10") (pintype "passive"))
      (node (ref "U1") (pin "19") (pinfunction "VSSA_19") (pintype "passive"))
      (node (ref "U1") (pin "26") (pinfunction "VSS_26") (pintype "passive"))
      (node (ref "U1") (pin "49") (pinfunction "VSS_49") (pintype "passive"))
      (node (ref "U1") (pin "74") (pinfunction "VSS_74") (pintype "passive"))
      (node (ref "U1") (pin "99") (pinfunction "VSS_99") (pintype "passive"))
      (node (ref "U2") (pin "11") (pinfunction "EP_11") (pintype "passive"))
      (node (ref "U3") (pin "4") (pinfunction "GND_4") (pintype "passive"))
      (node (ref "U4") (pin "1") (pinfunction "GND_1") (pintype "passive"))
      (node (ref "X1") (pin "2") (pinfunction "GND_2") (pintype "passive"))
      (node (ref "X1") (pin "4") (pinfunction "GND_4") (pintype "passive"))
    )
    (net (code "50") (name "Net-(C25-Pad2)") (class "Default")
      (node (ref "C25") (pin "2") (pinfunction "2_2") (pintype "passive"))
      (node (ref "U1") (pin "48") (pinfunction "VCAP_48") (pintype "passive"))
    )
    (net (code "51") (name "Net-(C26-Pad2)") (class "Default")
      (node (ref "C26") (pin "2") (pinfunction "2_2") (pintype "passive"))
      (node (ref "U1") (pin "73") (pinfunction "VCAP_73") (pintype "passive"))
    )
    (net (code "52") (name "Net-(C30-Pad1)") (class "Default")
      (node (ref "C30") (pin "1") (pinfunction "1_1") (pintype "passive"))
      (node (ref "R7") (pin "1") (pinfunction "1_1") (pintype "passive"))
    )
    (net (code "53") (name "Net-(C35-Pad2)") (class "Default")
      (node (ref "C35") (pin "2") (pinfunction "2_2") (pintype "passive"))
      (node (ref "R12") (pin "2") (pinfunction "2_2") (pintype "passive"))
    )
    (net (code "54") (name "Net-(D1-PadA)") (class "Default")
      (node (ref "D1") (pin "A") (pinfunction "A_A") (pintype "passive"))
      (node (ref "R16") (pin "1") (pinfunction "1_1") (pintype "passive"))
    )
    (net (code "55") (name "Net-(D2-PadA)") (class "Default")
      (node (ref "D2") (pin "A") (pinfunction "A_A") (pintype "passive"))
      (node (ref "R17") (pin "1") (pinfunction "1_1") (pintype "passive"))
    )
    (net (code "56") (name "Net-(D3-PadA)") (class "Default")
      (node (ref "D3") (pin "A") (pinfunction "A_A") (pintype "passive"))
      (node (ref "R18") (pin "1") (pinfunction "1_1") (pintype "passive"))
    )
    (net (code "57") (name "Net-(D4-PadA)") (class "Default")
      (node (ref "D4") (pin "A") (pinfunction "A_A") (pintype "passive"))
      (node (ref "R19") (pin "1") (pinfunction "1_1") (pintype "passive"))
    )
    (net (code "58") (name "Net-(D5-PadA)") (class "Default")
      (node (ref "D5") (pin "A") (pinfunction "A_A") (pintype "passive"))
      (node (ref "R20") (pin "1") (pinfunction "1_1") (pintype "passive"))
    )
    (net (code "59") (name "Net-(M1-ANA)") (class "Default")
      (node (ref "J5") (pin "1") (pintype "passive"))
      (node (ref "M1") (pin "2") (pinfunction "ANA_2") (pintype "passive"))
    )
    (net (code "60") (name "Net-(Q1-G)") (class "Default")
      (node (ref "Q1") (pin "2") (pinfunction "G_2") (pintype "passive"))
      (node (ref "R6") (pin "2") (pinfunction "2_2") (pintype "passive"))
    )
    (net (code "61") (name "Net-(Q1-S)") (class "Default")
      (node (ref "C29") (pin "2") (pinfunction "2_2") (pintype "passive"))
      (node (ref "L1") (pin "1") (pinfunction "1_1") (pintype "passive"))
      (node (ref "Q1") (pin "1") (pinfunction "S_1") (pintype "passive"))
      (node (ref "Q2") (pin "3") (pinfunction "D_3") (pintype "passive"))
      (node (ref "U2") (pin "8") (pinfunction "SW_8") (pintype "passive"))
    )
    (net (code "62") (name "Net-(Q2-G)") (class "Default")
      (node (ref "Q2") (pin "2") (pinfunction "G_2") (pintype "passive"))
      (node (ref "R9") (pin "2") (pinfunction "2_2") (pintype "passive"))
    )
    (net (code "63") (name "Net-(U1-PA11)") (class "Default")
      (node (ref "C47") (pin "1") (pinfunction "1_1") (pintype "passive"))
      (node (ref "SW3") (pin "1") (pinfunction "1_1") (pintype "passive"))
      (node (ref "U1") (pin "70") (pinfunction "PA11_70") (pintype "passive"))
    )
    (net (code "64") (name "Net-(U1-PA12)") (class "Default")
      (node (ref "C48") (pin "1") (pinfunction "1_1") (pintype "passive"))
      (node (ref "SW2") (pin "1") (pinfunction "1_1") (pintype "passive"))
      (node (ref "U1") (pin "71") (pinfunction "PA12_71") (pintype "passive"))
    )
    (net (code "65") (name "Net-(U1-PB12)") (class "Default")
      (node (ref "J20") (pin "7") (pinfunction "7_7") (pintype "passive"))
      (node (ref "U1") (pin "51") (pinfunction "PB12_51") (pintype "passive"))
    )
    (net (code "66") (name "Net-(U1-PB13)") (class "Default")
      (node (ref "J20") (pin "6") (pinfunction "6_6") (pintype "passive"))
      (node (ref "U1") (pin "52") (pinfunction "PB13_52") (pintype "passive"))
    )
    (net (code "67") (name "Net-(U1-PB14)") (class "Default")
      (node (ref "J20") (pin "5") (pinfunction "5_5") (pintype "passive"))
      (node (ref "U1") (pin "53") (pinfunction "PB14_53") (pintype "passive"))
    )
    (net (code "68") (name "Net-(U1-PB15)") (class "Default")
      (node (ref "J20") (pin "4") (pinfunction "4_4") (pintype "passive"))
      (node (ref "U1") (pin "54") (pinfunction "PB15_54") (pintype "passive"))
    )
    (net (code "69") (name "Net-(U1-PD2)") (class "Default")
      (node (ref "R20") (pin "2") (pinfunction "2_2") (pintype "passive"))
      (node (ref "U1") (pin "83") (pinfunction "PD2_83") (pintype "passive"))
    )
    (net (code "70") (name "Net-(U1-PD3)") (class "Default")
      (node (ref "R19") (pin "2") (pinfunction "2_2") (pintype "passive"))
      (node (ref "U1") (pin "84") (pinfunction "PD3_84") (pintype "passive"))
    )
    (net (code "71") (name "Net-(U1-PD4)") (class "Default")
      (node (ref "R18") (pin "2") (pinfunction "2_2") (pintype "passive"))
      (node (ref "U1") (pin "85") (pinfunction "PD4_85") (pintype "passive"))
    )
    (net (code "72") (name "Net-(U1-PD5)") (class "Default")
      (node (ref "R17") (pin "2") (pinfunction "2_2") (pintype "passive"))
      (node (ref "U1") (pin "86") (pinfunction "PD5_86") (pintype "passive"))
    )
    (net (code "73") (name "Net-(U1-PD8)") (class "Default")
      (node (ref "J20") (pin "3") (pinfunction "3_3") (pintype "passive"))
      (node (ref "U1") (pin "55") (pinfunction "PD8_55") (pintype "passive"))
    )
    (net (code "74") (name "Net-(U1-PD9)") (class "Default")
      (node (ref "J20") (pin "2") (pinfunction "2_2") (pintype "passive"))
      (node (ref "U1") (pin "56") (pinfunction "PD9_56") (pintype "passive"))
    )
    (net (code "75") (name "Net-(U1-PD10)") (class "Default")
      (node (ref "J20") (pin "1") (pinfunction "1_1") (pintype "passive"))
      (node (ref "U1") (pin "57") (pinfunction "PD10_57") (pintype "passive"))
    )
    (net (code "76") (name "Net-(U2-BOOT)") (class "Default")
      (node (ref "C29") (pin "1") (pinfunction "1_1") (pintype "passive"))
      (node (ref "U2") (pin "6") (pinfunction "BOOT_6") (pintype "passive"))
    )
    (net (code "77") (name "Net-(U2-BP)") (class "Default")
      (node (ref "C24") (pin "1") (pinfunction "1_1") (pintype "passive"))
      (node (ref "U2") (pin "10") (pinfunction "BP_10") (pintype "passive"))
    )
    (net (code "78") (name "Net-(U2-COMP)") (class "Default")
      (node (ref "C35") (pin "1") (pinfunction "1_1") (pintype "passive"))
      (node (ref "C36") (pin "1") (pinfunction "1_1") (pintype "passive"))
      (node (ref "U2") (pin "4") (pinfunction "COMP_4") (pintype "passive"))
    )
    (net (code "79") (name "Net-(U2-EN{slash}SS)") (class "Default")
      (node (ref "C27") (pin "1") (pinfunction "1_1") (pintype "passive"))
      (node (ref "U2") (pin "2") (pinfunction "EN/SS_2") (pintype "passive"))
    )
    (net (code "80") (name "Net-(U2-FB)") (class "Default")
      (node (ref "C30") (pin "2") (pinfunction "2_2") (pintype "passive"))
      (node (ref "C36") (pin "2") (pinfunction "2_2") (pintype "passive"))
      (node (ref "R10") (pin "2") (pinfunction "2_2") (pintype "passive"))
      (node (ref "R12") (pin "1") (pinfunction "1_1") (pintype "passive"))
      (node (ref "R8") (pin "1") (pinfunction "1_1") (pintype "passive"))
      (node (ref "U2") (pin "5") (pinfunction "FB_5") (pintype "passive"))
    )
    (net (code "81") (name "Net-(U2-HDRV)") (class "Default")
      (node (ref "R6") (pin "1") (pinfunction "1_1") (pintype "passive"))
      (node (ref "U2") (pin "7") (pinfunction "HDRV_7") (pintype "passive"))
    )
    (net (code "82") (name "Net-(U2-LDRV{slash}OC)") (class "Default")
      (node (ref "R11") (pin "2") (pinfunction "2_2") (pintype "passive"))
      (node (ref "R9") (pin "1") (pinfunction "1_1") (pintype "passive"))
      (node (ref "U2") (pin "9") (pinfunction "LDRV/OC_9") (pintype "passive"))
    )
    (net (code "83") (name "Net-(U4-SW)") (class "Default")
      (node (ref "C38") (pin "1") (pinfunction "1_1") (pintype "passive"))
      (node (ref "L2") (pin "1") (pinfunction "1_1") (pintype "passive"))
      (node (ref "U4") (pin "2") (pinfunction "SW_2") (pintype "passive"))
    )
    (net (code "84") (name "Net-(U4-VBST)") (class "Default")
      (node (ref "C38") (pin "2") (pinfunction "2_2") (pintype "passive"))
      (node (ref "U4") (pin "6") (pinfunction "VBST_6") (pintype "passive"))
    )
    (net (code "85") (name "Net-(U4-VFB)") (class "Default")
      (node (ref "C42") (pin "1") (pinfunction "1_1") (pintype "passive"))
      (node (ref "R14") (pin "1") (pinfunction "1_1") (pintype "passive"))
      (node (ref "R15") (pin "2") (pinfunction "2_2") (pintype "passive"))
      (node (ref "U4") (pin "4") (pinfunction "VFB_4") (pintype "passive"))
    )
    (net (code "86") (name "unconnected-(J17-Pad4)") (class "Default")
      (node (ref "J17") (pin "4") (pinfunction "4_4") (pintype "passive"))
    )
    (net (code "87") (name "unconnected-(J18-Pad0)") (class "Default")
      (node (ref "J18") (pin "0") (pinfunction "0_0") (pintype "passive"))
    )
    (net (code "88") (name "unconnected-(J19-Pad0)") (class "Default")
      (node (ref "J19") (pin "0") (pinfunction "0_0") (pintype "passive"))
    )
    (net (code "89") (name "unconnected-(J21-Pad1)") (class "Default")
      (node (ref "J21") (pin "1") (pinfunction "1_1") (pintype "passive"))
    )
    (net (code "90") (name "unconnected-(J21-Pad2)") (class "Default")
      (node (ref "J21") (pin "2") (pinfunction "2_2") (pintype "passive"))
    )
    (net (code "91") (name "unconnected-(J21-Pad3)") (class "Default")
      (node (ref "J21") (pin "3") (pinfunction "3_3") (pintype "passive"))
    )
    (net (code "92") (name "unconnected-(J21-Pad4)") (class "Default")
      (node (ref "J21") (pin "4") (pinfunction "4_4") (pintype "passive"))
    )
    (net (code "93") (name "unconnected-(M1-DIO0-Pad10)") (class "Default")
      (node (ref "M1") (pin "10") (pinfunction "DIO0_10") (pintype "passive"))
    )
    (net (code "94") (name "unconnected-(M1-DIO1-Pad11)") (class "Default")
      (node (ref "M1") (pin "11") (pinfunction "DIO1_11") (pintype "passive"))
    )
    (net (code "95") (name "unconnected-(M1-DIO2-Pad12)") (class "Default")
      (node (ref "M1") (pin "12") (pinfunction "DIO2_12") (pintype "passive"))
    )
    (net (code "96") (name "unconnected-(M1-DIO3-Pad13)") (class "Default")
      (node (ref "M1") (pin "13") (pinfunction "DIO3_13") (pintype "passive"))
    )
    (net (code "97") (name "unconnected-(M1-DIO4-Pad14)") (class "Default")
      (node (ref "M1") (pin "14") (pinfunction "DIO4_14") (pintype "passive"))
    )
    (net (code "98") (name "unconnected-(M1-DIO5-Pad15)") (class "Default")
      (node (ref "M1") (pin "15") (pinfunction "DIO5_15") (pintype "passive"))
    )
    (net (code "99") (name "unconnected-(M1-NC-Pad8)") (class "Default")
      (node (ref "M1") (pin "8") (pinfunction "NC_8") (pintype "passive"))
    )
    (net (code "100") (name "unconnected-(U1-PA4-Pad28)") (class "Default")
      (node (ref "U1") (pin "28") (pinfunction "PA4_28") (pintype "passive"))
    )
    (net (code "101") (name "unconnected-(U1-PA8-Pad67)") (class "Default")
      (node (ref "U1") (pin "67") (pinfunction "PA8_67") (pintype "passive"))
    )
    (net (code "102") (name "unconnected-(U1-PA15-Pad77)") (class "Default")
      (node (ref "U1") (pin "77") (pinfunction "PA15_77") (pintype "passive"))
    )
    (net (code "103") (name "unconnected-(U1-PB0-Pad34)") (class "Default")
      (node (ref "U1") (pin "34") (pinfunction "PB0_34") (pintype "passive"))
    )
    (net (code "104") (name "unconnected-(U1-PB1-Pad35)") (class "Default")
      (node (ref "U1") (pin "35") (pinfunction "PB1_35") (pintype "passive"))
    )
    (net (code "105") (name "unconnected-(U1-PB6-Pad92)") (class "Default")
      (node (ref "U1") (pin "92") (pinfunction "PB6_92") (pintype "passive"))
    )
    (net (code "106") (name "unconnected-(U1-PB7-Pad93)") (class "Default")
      (node (ref "U1") (pin "93") (pinfunction "PB7_93") (pintype "passive"))
    )
    (net (code "107") (name "unconnected-(U1-PB8-Pad95)") (class "Default")
      (node (ref "U1") (pin "95") (pinfunction "PB8_95") (pintype "passive"))
    )
    (net (code "108") (name "unconnected-(U1-PB9-Pad96)") (class "Default")
      (node (ref "U1") (pin "96") (pinfunction "PB9_96") (pintype "passive"))
    )
    (net (code "109") (name "unconnected-(U1-PB11-Pad47)") (class "Default")
      (node (ref "U1") (pin "47") (pinfunction "PB11_47") (pintype "passive"))
    )
    (net (code "110") (name "unconnected-(U1-PC0-Pad15)") (class "Default")
      (node (ref "U1") (pin "15") (pinfunction "PC0_15") (pintype "passive"))
    )
    (net (code "111") (name "unconnected-(U1-PC1-Pad16)") (class "Default")
      (node (ref "U1") (pin "16") (pinfunction "PC1_16") (pintype "passive"))
    )
    (net (code "112") (name "unconnected-(U1-PC2_C-Pad17)") (class "Default")
      (node (ref "U1") (pin "17") (pinfunction "PC2_C_17") (pintype "passive"))
    )
    (net (code "113") (name "unconnected-(U1-PC3_C-Pad18)") (class "Default")
      (node (ref "U1") (pin "18") (pinfunction "PC3_C_18") (pintype "passive"))
    )
    (net (code "114") (name "unconnected-(U1-PC13-Pad7)") (class "Default")
      (node (ref "U1") (pin "7") (pinfunction "PC13_7") (pintype "passive"))
    )
    (net (code "115") (name "unconnected-(U1-PC14-OSC32_IN-Pad8)") (class "Default")
      (node (ref "U1") (pin "8") (pinfunction "PC14-OSC32_IN_8") (pintype "passive"))
    )
    (net (code "116") (name "unconnected-(U1-PC15-OSC32_OUT-Pad9)") (class "Default")
      (node (ref "U1") (pin "9") (pinfunction "PC15-OSC32_OUT_9") (pintype "passive"))
    )
    (net (code "117") (name "unconnected-(U1-PD13-Pad60)") (class "Default")
      (node (ref "U1") (pin "60") (pinfunction "PD13_60") (pintype "passive"))
    )
    (net (code "118") (name "unconnected-(U1-PE0-Pad97)") (class "Default")
      (node (ref "U1") (pin "97") (pinfunction "PE0_97") (pintype "passive"))
    )
    (net (code "119") (name "unconnected-(U1-PE1-Pad98)") (class "Default")
      (node (ref "U1") (pin "98") (pinfunction "PE1_98") (pintype "passive"))
    )
    (net (code "120") (name "unconnected-(U1-PE2-Pad1)") (class "Default")
      (node (ref "U1") (pin "1") (pinfunction "PE2_1") (pintype "passive"))
    )
    (net (code "121") (name "unconnected-(U1-PE3-Pad2)") (class "Default")
      (node (ref "U1") (pin "2") (pinfunction "PE3_2") (pintype "passive"))
    )
    (net (code "122") (name "unconnected-(U1-PE4-Pad3)") (class "Default")
      (node (ref "U1") (pin "3") (pinfunction "PE4_3") (pintype "passive"))
    )
    (net (code "123") (name "unconnected-(U1-PE5-Pad4)") (class "Default")
      (node (ref "U1") (pin "4") (pinfunction "PE5_4") (pintype "passive"))
    )
    (net (code "124") (name "unconnected-(U1-PE6-Pad5)") (class "Default")
      (node (ref "U1") (pin "5") (pinfunction "PE6_5") (pintype "passive"))
    )
    (net (code "125") (name "unconnected-(U1-PE7-Pad37)") (class "Default")
      (node (ref "U1") (pin "37") (pinfunction "PE7_37") (pintype "passive"))
    )
    (net (code "126") (name "unconnected-(U1-VBAT-Pad6)") (class "Default")
      (node (ref "U1") (pin "6") (pinfunction "VBAT_6") (pintype "passive"))
    )
    (net (code "127") (name "unconnected-(U2-PGOOD-Pad3)") (class "Default")
      (node (ref "U2") (pin "3") (pinfunction "PGOOD_3") (pintype "passive"))
    )
    (net (code "128") (name "unconnected-(U3-IO2-Pad3)") (class "Default")
      (node (ref "U3") (pin "3") (pinfunction "IO2_3") (pintype "passive"))
    )
    (net (code "129") (name "unconnected-(U3-IO3-Pad7)") (class "Default")
      (node (ref "U3") (pin "7") (pinfunction "IO3_7") (pintype "passive"))
    )
  )
)
